# transmitter_with_sensor.net
KiCad netlist of a schematic drawn in EAGLE
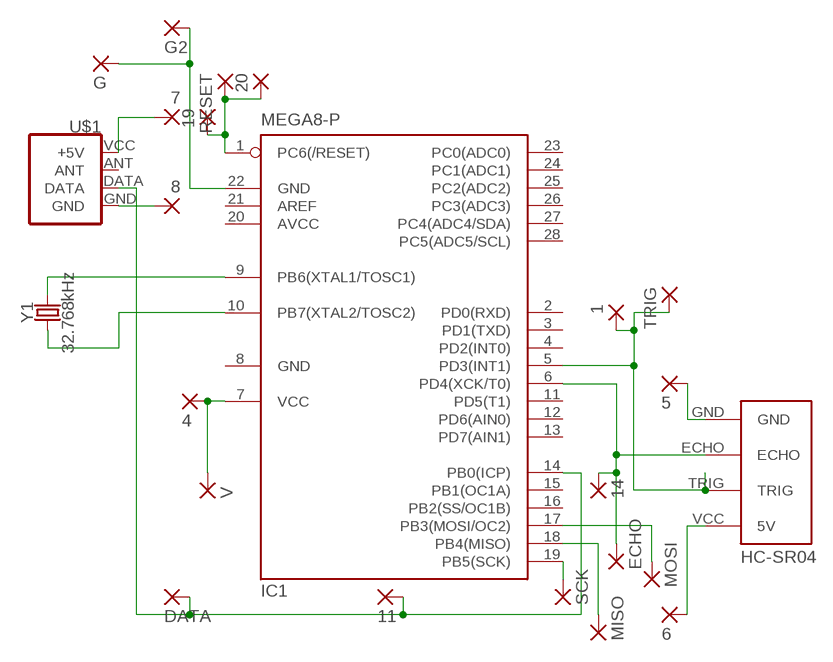
[diagram p0: schematic, sheet 1]

(export (version "E")
  (design (tool "Eeschema 10.0.6"))
  (components
    (comp (ref "1")
      (value "WIREPAD1,6/0,8")
      (footprint "eagle-import:1,6_0,8")
      (libsource (lib "eagle-import") (part "WIREPAD1,6/0,8"))
    )
    (comp (ref "4")
      (value "WIREPAD1,6/0,8")
      (footprint "eagle-import:1,6_0,8")
      (libsource (lib "eagle-import") (part "WIREPAD1,6/0,8"))
    )
    (comp (ref "5")
      (value "WIREPAD1,6/0,8")
      (footprint "eagle-import:1,6_0,8")
      (libsource (lib "eagle-import") (part "WIREPAD1,6/0,8"))
    )
    (comp (ref "6")
      (value "WIREPAD1,6/0,8")
      (footprint "eagle-import:1,6_0,8")
      (libsource (lib "eagle-import") (part "WIREPAD1,6/0,8"))
    )
    (comp (ref "7")
      (value "WIREPAD1,6/0,8")
      (footprint "eagle-import:1,6_0,8")
      (libsource (lib "eagle-import") (part "WIREPAD1,6/0,8"))
    )
    (comp (ref "8")
      (value "WIREPAD1,6/0,8")
      (footprint "eagle-import:1,6_0,8")
      (libsource (lib "eagle-import") (part "WIREPAD1,6/0,8"))
    )
    (comp (ref "11")
      (value "WIREPAD1,6/0,8")
      (footprint "eagle-import:1,6_0,8")
      (libsource (lib "eagle-import") (part "WIREPAD1,6/0,8"))
    )
    (comp (ref "14")
      (value "WIREPAD1,6/0,8")
      (footprint "eagle-import:1,6_0,8")
      (libsource (lib "eagle-import") (part "WIREPAD1,6/0,8"))
    )
    (comp (ref "19")
      (value "WIREPAD1,6/0,8")
      (footprint "eagle-import:1,6_0,8")
      (libsource (lib "eagle-import") (part "WIREPAD1,6/0,8"))
    )
    (comp (ref "20")
      (value "WIREPAD1,6/0,8")
      (footprint "eagle-import:1,6_0,8")
      (libsource (lib "eagle-import") (part "WIREPAD1,6/0,8"))
    )
    (comp (ref "DATA")
      (value "WIREPAD1,6/0,8")
      (footprint "eagle-import:1,6_0,8")
      (libsource (lib "eagle-import") (part "WIREPAD1,6/0,8"))
    )
    (comp (ref "ECHO")
      (value "WIREPAD1,6/0,8")
      (footprint "eagle-import:1,6_0,8")
      (libsource (lib "eagle-import") (part "WIREPAD1,6/0,8"))
    )
    (comp (ref "G")
      (value "WIREPAD1,6/0,8")
      (footprint "eagle-import:1,6_0,8")
      (libsource (lib "eagle-import") (part "WIREPAD1,6/0,8"))
    )
    (comp (ref "G2")
      (value "WIREPAD1,6/0,8")
      (footprint "eagle-import:1,6_0,8")
      (libsource (lib "eagle-import") (part "WIREPAD1,6/0,8"))
    )
    (comp (ref "IC1")
      (value "MEGA8-P")
      (footprint "eagle-import:DIL28-3")
      (libsource (lib "eagle-import") (part "MEGA8-P"))
    )
    (comp (ref "J_ULTRASONIC_1")
      (value "HC-SR04")
      (footprint "eagle-import:HC-SR04_FOOTPRINT")
      (libsource (lib "eagle-import") (part "HC-SR04"))
    )
    (comp (ref "MISO")
      (value "WIREPAD1,6/0,8")
      (footprint "eagle-import:1,6_0,8")
      (libsource (lib "eagle-import") (part "WIREPAD1,6/0,8"))
    )
    (comp (ref "MOSI")
      (value "WIREPAD1,6/0,8")
      (footprint "eagle-import:1,6_0,8")
      (libsource (lib "eagle-import") (part "WIREPAD1,6/0,8"))
    )
    (comp (ref "RESET")
      (value "WIREPAD1,6/0,8")
      (footprint "eagle-import:1,6_0,8")
      (libsource (lib "eagle-import") (part "WIREPAD1,6/0,8"))
    )
    (comp (ref "SCK")
      (value "WIREPAD1,6/0,8")
      (footprint "eagle-import:1,6_0,8")
      (libsource (lib "eagle-import") (part "WIREPAD1,6/0,8"))
    )
    (comp (ref "TRIG")
      (value "WIREPAD1,6/0,8")
      (footprint "eagle-import:1,6_0,8")
      (libsource (lib "eagle-import") (part "WIREPAD1,6/0,8"))
    )
    (comp (ref "U$1")
      (value "RF-LINK_TX")
      (footprint "eagle-import:RF-LINK_TX")
      (libsource (lib "eagle-import") (part "RF-LINK_TX"))
    )
    (comp (ref "V")
      (value "WIREPAD1,6/0,8")
      (footprint "eagle-import:1,6_0,8")
      (libsource (lib "eagle-import") (part "WIREPAD1,6/0,8"))
    )
    (comp (ref "Y1")
      (value "32.768kHz")
      (footprint "eagle-import:CRYSTAL-PTH-2X6-CYL")
      (libsource (lib "eagle-import") (part "CRYSTAL-32.768KHZPTH-2X6"))
    )
  )
  (nets
    (net (code "1") (name "/AVCC") (class "Default")
      (node (ref "IC1") (pin "20") (pinfunction "AVCC_20") (pintype "power_in"))
    )
    (net (code "2") (name "/GND") (class "Default")
      (node (ref "IC1") (pin "8") (pinfunction "GND_8") (pintype "power_in"))
    )
    (net (code "3") (name "Net-(1-P)") (class "Default")
      (node (ref "1") (pin "1") (pinfunction "P_1") (pintype "passive"))
      (node (ref "IC1") (pin "5") (pinfunction "PD3(INT1)_5") (pintype "bidirectional"))
      (node (ref "J_ULTRASONIC_1") (pin "TRIG") (pinfunction "TRIG_TRIG") (pintype "bidirectional"))
      (node (ref "TRIG") (pin "1") (pinfunction "P_1") (pintype "passive"))
    )
    (net (code "4") (name "Net-(4-P)") (class "Default")
      (node (ref "4") (pin "1") (pinfunction "P_1") (pintype "passive"))
      (node (ref "IC1") (pin "7") (pinfunction "VCC_7") (pintype "power_in"))
      (node (ref "V") (pin "1") (pinfunction "P_1") (pintype "passive"))
    )
    (net (code "5") (name "Net-(5-P)") (class "Default")
      (node (ref "5") (pin "1") (pinfunction "P_1") (pintype "passive"))
      (node (ref "J_ULTRASONIC_1") (pin "GND") (pinfunction "GND_GND") (pintype "bidirectional"))
    )
    (net (code "6") (name "Net-(6-P)") (class "Default")
      (node (ref "6") (pin "1") (pinfunction "P_1") (pintype "passive"))
      (node (ref "J_ULTRASONIC_1") (pin "VCC") (pinfunction "5V_VCC") (pintype "bidirectional"))
    )
    (net (code "7") (name "Net-(7-P)") (class "Default")
      (node (ref "7") (pin "1") (pinfunction "P_1") (pintype "passive"))
      (node (ref "U$1") (pin "VCC") (pinfunction "+5V_VCC") (pintype "power_in"))
    )
    (net (code "8") (name "Net-(8-P)") (class "Default")
      (node (ref "8") (pin "1") (pinfunction "P_1") (pintype "passive"))
      (node (ref "U$1") (pin "GND") (pinfunction "GND_GND") (pintype "power_in"))
    )
    (net (code "9") (name "Net-(11-P)") (class "Default")
      (node (ref "11") (pin "1") (pinfunction "P_1") (pintype "passive"))
      (node (ref "DATA") (pin "1") (pinfunction "P_1") (pintype "passive"))
      (node (ref "IC1") (pin "14") (pinfunction "PB0(ICP)_14") (pintype "bidirectional"))
      (node (ref "U$1") (pin "DATA") (pinfunction "DATA_DATA") (pintype "input"))
    )
    (net (code "10") (name "Net-(14-P)") (class "Default")
      (node (ref "14") (pin "1") (pinfunction "P_1") (pintype "passive"))
      (node (ref "ECHO") (pin "1") (pinfunction "P_1") (pintype "passive"))
      (node (ref "IC1") (pin "6") (pinfunction "PD4(XCK/T0)_6") (pintype "bidirectional"))
      (node (ref "J_ULTRASONIC_1") (pin "ECHO") (pinfunction "ECHO_ECHO") (pintype "bidirectional"))
    )
    (net (code "11") (name "Net-(19-P)") (class "Default")
      (node (ref "19") (pin "1") (pinfunction "P_1") (pintype "passive"))
      (node (ref "20") (pin "1") (pinfunction "P_1") (pintype "passive"))
      (node (ref "IC1") (pin "1") (pinfunction "PC6(/RESET)_1") (pintype "bidirectional"))
      (node (ref "RESET") (pin "1") (pinfunction "P_1") (pintype "passive"))
    )
    (net (code "12") (name "Net-(G-P)") (class "Default")
      (node (ref "G") (pin "1") (pinfunction "P_1") (pintype "passive"))
      (node (ref "G2") (pin "1") (pinfunction "P_1") (pintype "passive"))
      (node (ref "IC1") (pin "22") (pinfunction "GND_22") (pintype "power_in"))
    )
    (net (code "13") (name "Net-(IC1-PB3(MOSI{slash}OC2))") (class "Default")
      (node (ref "IC1") (pin "17") (pinfunction "PB3(MOSI/OC2)_17") (pintype "bidirectional"))
      (node (ref "MOSI") (pin "1") (pinfunction "P_1") (pintype "passive"))
    )
    (net (code "14") (name "Net-(IC1-PB4(MISO))") (class "Default")
      (node (ref "IC1") (pin "18") (pinfunction "PB4(MISO)_18") (pintype "bidirectional"))
      (node (ref "MISO") (pin "1") (pinfunction "P_1") (pintype "passive"))
    )
    (net (code "15") (name "Net-(IC1-PB5(SCK))") (class "Default")
      (node (ref "IC1") (pin "19") (pinfunction "PB5(SCK)_19") (pintype "bidirectional"))
      (node (ref "SCK") (pin "1") (pinfunction "P_1") (pintype "passive"))
    )
    (net (code "16") (name "Net-(IC1-PB6(XTAL1{slash}TOSC1))") (class "Default")
      (node (ref "IC1") (pin "9") (pinfunction "PB6(XTAL1/TOSC1)_9") (pintype "bidirectional"))
      (node (ref "Y1") (pin "2") (pinfunction "2_2") (pintype "passive"))
    )
    (net (code "17") (name "Net-(IC1-PB7(XTAL2{slash}TOSC2))") (class "Default")
      (node (ref "IC1") (pin "10") (pinfunction "PB7(XTAL2/TOSC2)_10") (pintype "bidirectional"))
      (node (ref "Y1") (pin "1") (pinfunction "1_1") (pintype "passive"))
    )
    (net (code "18") (name "unconnected-(IC1-AREF-Pad21)") (class "Default")
      (node (ref "IC1") (pin "21") (pinfunction "AREF_21") (pintype "passive"))
    )
    (net (code "19") (name "unconnected-(IC1-PB1(OC1A)-Pad15)") (class "Default")
      (node (ref "IC1") (pin "15") (pinfunction "PB1(OC1A)_15") (pintype "bidirectional"))
    )
    (net (code "20") (name "unconnected-(IC1-PB2(SS{slash}OC1B)-Pad16)") (class "Default")
      (node (ref "IC1") (pin "16") (pinfunction "PB2(SS/OC1B)_16") (pintype "bidirectional"))
    )
    (net (code "21") (name "unconnected-(IC1-PC0(ADC0)-Pad23)") (class "Default")
      (node (ref "IC1") (pin "23") (pinfunction "PC0(ADC0)_23") (pintype "bidirectional"))
    )
    (net (code "22") (name "unconnected-(IC1-PC1(ADC1)-Pad24)") (class "Default")
      (node (ref "IC1") (pin "24") (pinfunction "PC1(ADC1)_24") (pintype "bidirectional"))
    )
    (net (code "23") (name "unconnected-(IC1-PC2(ADC2)-Pad25)") (class "Default")
      (node (ref "IC1") (pin "25") (pinfunction "PC2(ADC2)_25") (pintype "bidirectional"))
    )
    (net (code "24") (name "unconnected-(IC1-PC3(ADC3)-Pad26)") (class "Default")
      (node (ref "IC1") (pin "26") (pinfunction "PC3(ADC3)_26") (pintype "bidirectional"))
    )
    (net (code "25") (name "unconnected-(IC1-PC4(ADC4{slash}SDA)-Pad27)") (class "Default")
      (node (ref "IC1") (pin "27") (pinfunction "PC4(ADC4/SDA)_27") (pintype "bidirectional"))
    )
    (net (code "26") (name "unconnected-(IC1-PC5(ADC5{slash}SCL)-Pad28)") (class "Default")
      (node (ref "IC1") (pin "28") (pinfunction "PC5(ADC5/SCL)_28") (pintype "bidirectional"))
    )
    (net (code "27") (name "unconnected-(IC1-PD0(RXD)-Pad2)") (class "Default")
      (node (ref "IC1") (pin "2") (pinfunction "PD0(RXD)_2") (pintype "bidirectional"))
    )
    (net (code "28") (name "unconnected-(IC1-PD1(TXD)-Pad3)") (class "Default")
      (node (ref "IC1") (pin "3") (pinfunction "PD1(TXD)_3") (pintype "bidirectional"))
    )
    (net (code "29") (name "unconnected-(IC1-PD2(INT0)-Pad4)") (class "Default")
      (node (ref "IC1") (pin "4") (pinfunction "PD2(INT0)_4") (pintype "bidirectional"))
    )
    (net (code "30") (name "unconnected-(IC1-PD5(T1)-Pad11)") (class "Default")
      (node (ref "IC1") (pin "11") (pinfunction "PD5(T1)_11") (pintype "bidirectional"))
    )
    (net (code "31") (name "unconnected-(IC1-PD6(AIN0)-Pad12)") (class "Default")
      (node (ref "IC1") (pin "12") (pinfunction "PD6(AIN0)_12") (pintype "bidirectional"))
    )
    (net (code "32") (name "unconnected-(IC1-PD7(AIN1)-Pad13)") (class "Default")
      (node (ref "IC1") (pin "13") (pinfunction "PD7(AIN1)_13") (pintype "bidirectional"))
    )
    (net (code "33") (name "unconnected-(U$1-PadANT)") (class "Default")
      (node (ref "U$1") (pin "ANT") (pinfunction "ANT_ANT") (pintype "passive"))
    )
  )
)
